# SCH_ODO_2025-04-28.net
KiCad netlist of a schematic drawn in EasyEDA
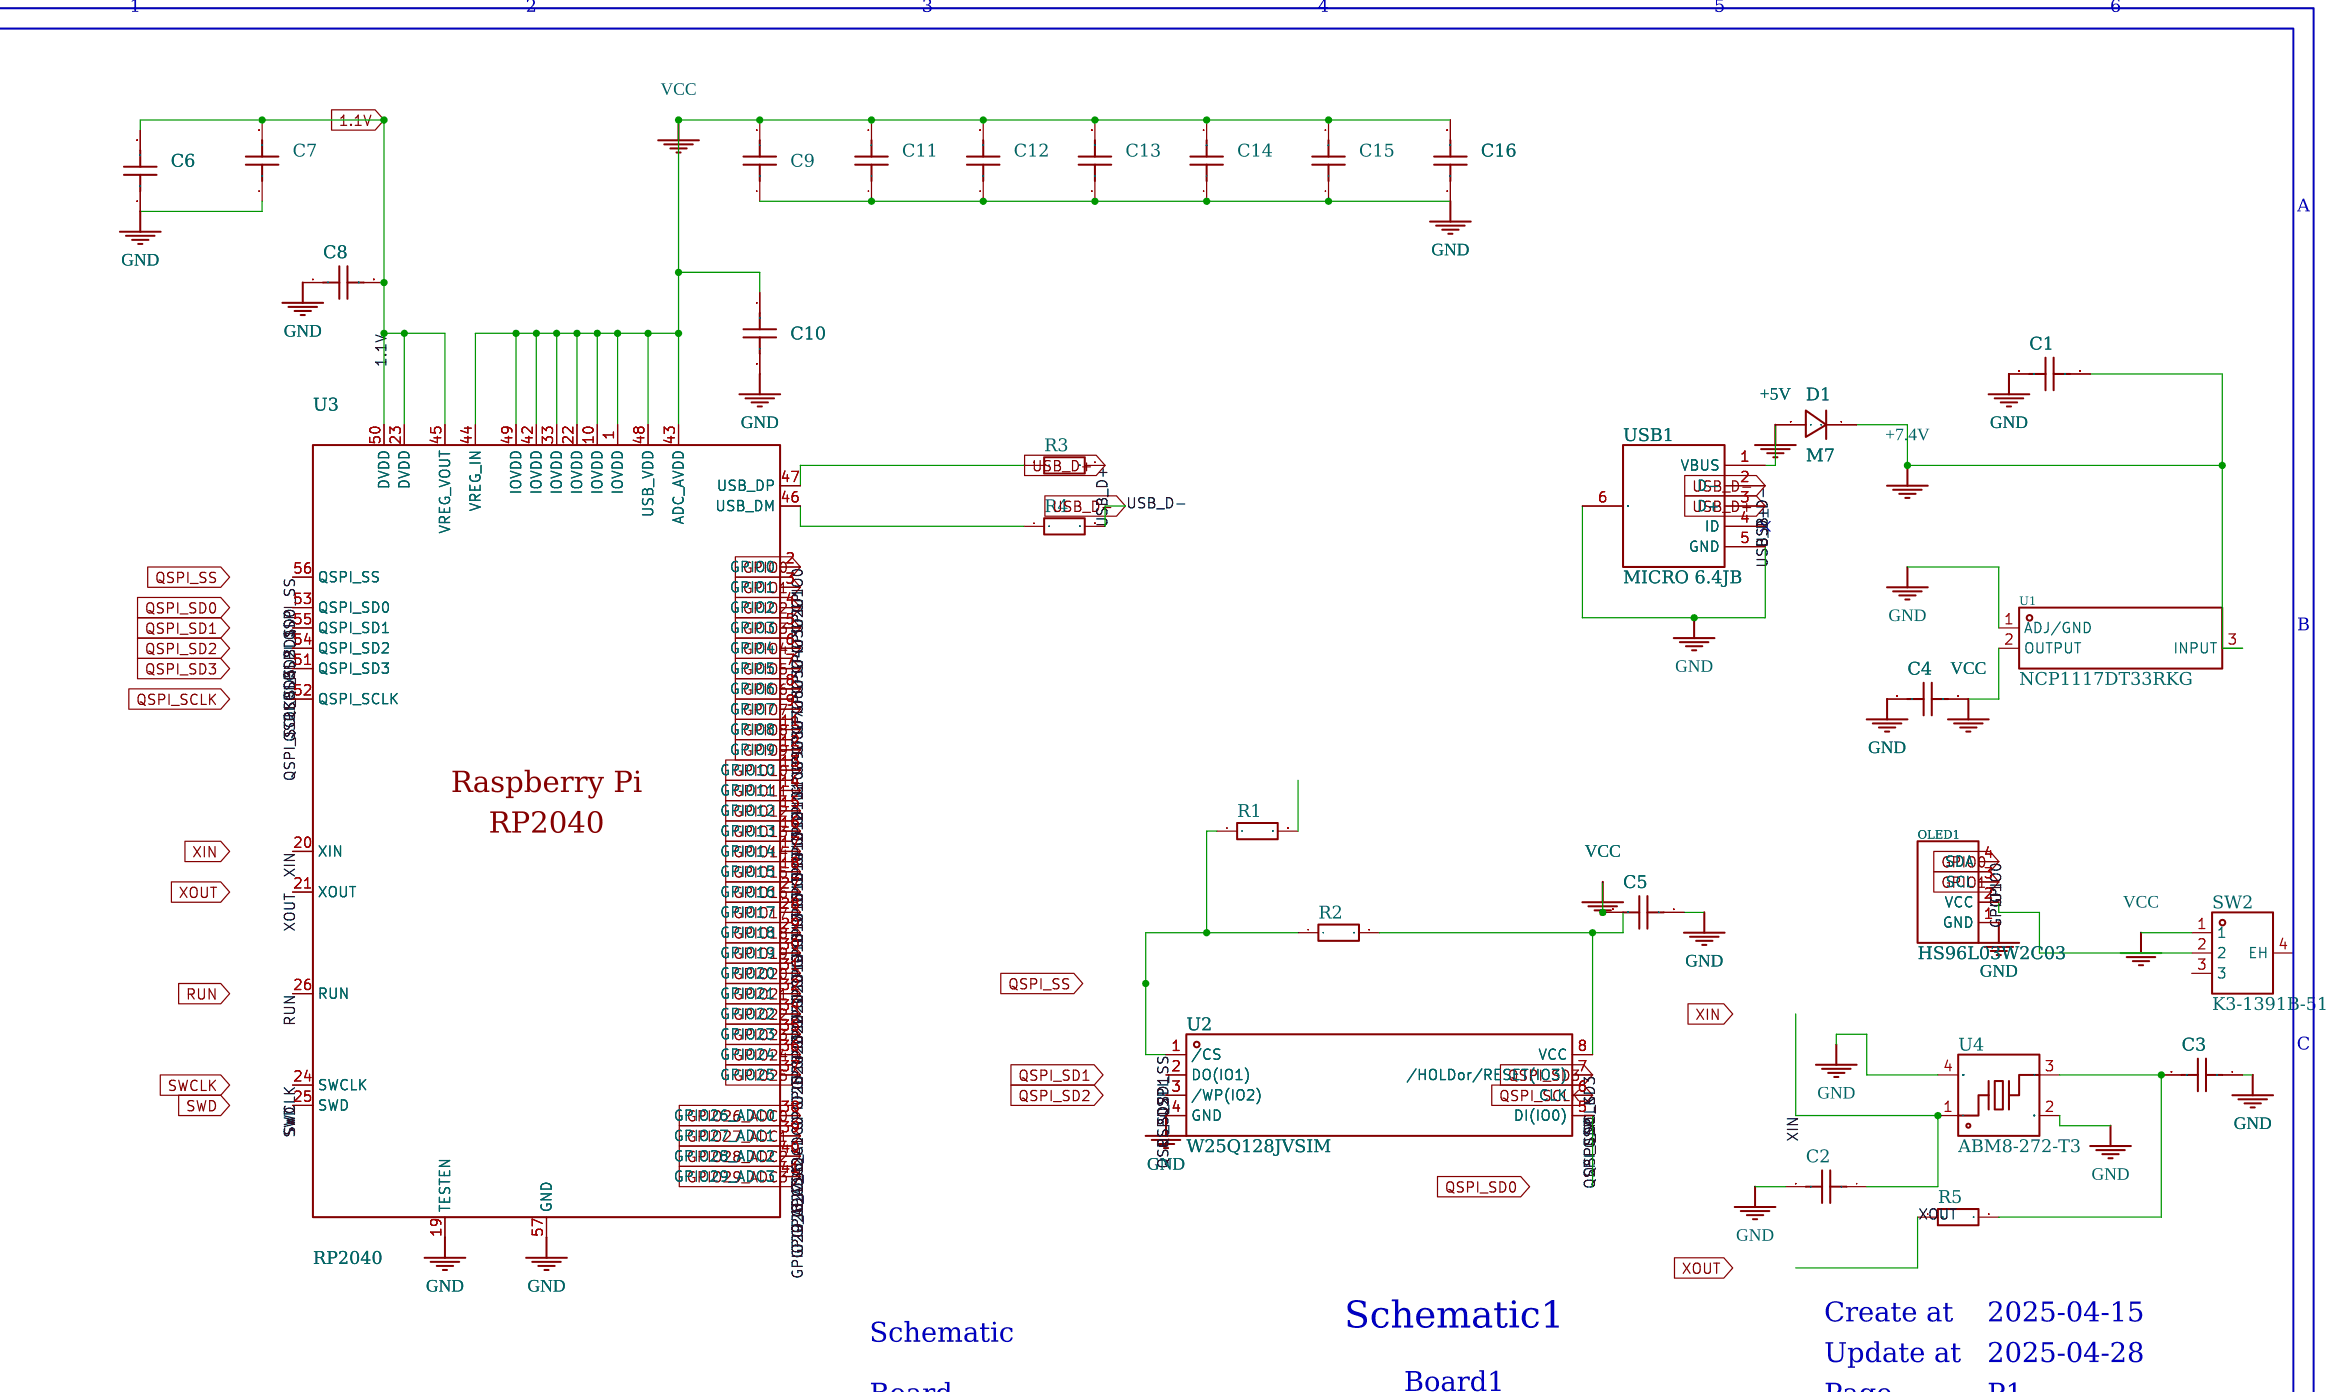
[diagram p0: schematic sheet]

(export (version "E")
  (design (tool "Eeschema 10.0.6"))
  (components
    (comp (ref "C1") (value "10uF") (libsource (lib "") (part "Unknown_1060_-665")))
    (comp (ref "C2") (value "15pF") (libsource (lib "") (part "Unknown_950_-265")))
    (comp (ref "C3") (value "15pF") (libsource (lib "") (part "Unknown_1135_-320")))
    (comp (ref "C4") (value "10uF") (libsource (lib "") (part "Unknown_1000_-505")))
    (comp (ref "C5")
      (value "100nF")
      (fields
        (field (name "Manufacturer Part") "CL05B104KO5NNNC")
        (field (name "Manufacturer") "SAMSUNG(三星)")
      )
      (libsource (lib "") (part "Unknown_860_-400"))
    )
    (comp (ref "C6")
      (value "100nF")
      (fields
        (field (name "Manufacturer Part") "CL05B104KO5NNNC")
        (field (name "Manufacturer") "SAMSUNG(三星)")
      )
      (libsource (lib "") (part "Unknown_120_-765"))
    )
    (comp (ref "C7")
      (value "100nF")
      (fields
        (field (name "Manufacturer Part") "CL05B104KO5NNNC")
        (field (name "Manufacturer") "SAMSUNG(三星)")
      )
      (libsource (lib "") (part "Unknown_180_-770"))
    )
    (comp (ref "C8")
      (value "1uF")
      (fields
        (field (name "Manufacturer Part") "CL05A105KA5NQNC")
        (field (name "Manufacturer") "SAMSUNG(三星)")
      )
      (libsource (lib "") (part "Unknown_220_-710"))
    )
    (comp (ref "C9")
      (value "100nF")
      (fields
        (field (name "Manufacturer Part") "CL05B104KO5NNNC")
        (field (name "Manufacturer") "SAMSUNG(三星)")
      )
      (libsource (lib "") (part "Unknown_425_-770"))
    )
    (comp (ref "C10")
      (value "1uF")
      (fields
        (field (name "Manufacturer Part") "CL05A105KA5NQNC")
        (field (name "Manufacturer") "SAMSUNG(三星)")
      )
      (libsource (lib "") (part "Unknown_425_-685"))
    )
    (comp (ref "C11")
      (value "100nF")
      (fields
        (field (name "Manufacturer Part") "CL05B104KO5NNNC")
        (field (name "Manufacturer") "SAMSUNG(三星)")
      )
      (libsource (lib "") (part "Unknown_480_-770"))
    )
    (comp (ref "C12")
      (value "100nF")
      (fields
        (field (name "Manufacturer Part") "CL05B104KO5NNNC")
        (field (name "Manufacturer") "SAMSUNG(三星)")
      )
      (libsource (lib "") (part "Unknown_535_-770"))
    )
    (comp (ref "C13")
      (value "100nF")
      (fields
        (field (name "Manufacturer Part") "CL05B104KO5NNNC")
        (field (name "Manufacturer") "SAMSUNG(三星)")
      )
      (libsource (lib "") (part "Unknown_590_-770"))
    )
    (comp (ref "C14")
      (value "100nF")
      (fields
        (field (name "Manufacturer Part") "CL05B104KO5NNNC")
        (field (name "Manufacturer") "SAMSUNG(三星)")
      )
      (libsource (lib "") (part "Unknown_645_-770"))
    )
    (comp (ref "C15")
      (value "100nF")
      (fields
        (field (name "Manufacturer Part") "CL05B104KO5NNNC")
        (field (name "Manufacturer") "SAMSUNG(三星)")
      )
      (libsource (lib "") (part "Unknown_705_-770"))
    )
    (comp (ref "C16")
      (value "100nF")
      (fields
        (field (name "Manufacturer Part") "CL05B104KO5NNNC")
        (field (name "Manufacturer") "SAMSUNG(三星)")
      )
      (libsource (lib "") (part "Unknown_765_-770"))
    )
    (comp (ref "D1")
      (value "M7")
      (fields (field (name "Manufacturer") "MDD(辰达半导体)"))
      (libsource (lib "") (part "Unknown_945_-640"))
    )
    (comp (ref "OLED1")
      (value "HS96L03W2C03")
      (fields (field (name "Manufacturer") "HS(汉昇)"))
      (libsource (lib "") (part "Unknown_1015_-410"))
    )
    (comp (ref "R1") (value "1K") (libsource (lib "") (part "Unknown_670_-440")))
    (comp (ref "R2") (value "10K") (libsource (lib "") (part "Unknown_710_-390")))
    (comp (ref "R3") (value "27") (libsource (lib "") (part "Unknown_575_-620")))
    (comp (ref "R4") (value "27") (libsource (lib "") (part "Unknown_575_-590")))
    (comp (ref "R5") (value "1K") (libsource (lib "") (part "Unknown_1015_-250")))
    (comp (ref "SW2")
      (value "K3-1391B-51")
      (fields (field (name "Manufacturer") "韩国韩荣"))
      (libsource (lib "") (part "Unknown_1155_-380"))
    )
    (comp (ref "U1")
      (value "NCP1117DT33RKG")
      (fields (field (name "Manufacturer") "onsemi(安森美)"))
      (libsource (lib "") (part "Unknown_1095_-535"))
    )
    (comp (ref "U2")
      (value "W25Q128JVSIM")
      (fields (field (name "Manufacturer") "WINBOND(华邦)"))
      (libsource (lib "") (part "Unknown_730_-315"))
    )
    (comp (ref "U3")
      (value "RP2040")
      (fields (field (name "Manufacturer") "Raspberry Pi(树莓派)"))
      (libsource (lib "") (part "Unknown_320_-430"))
    )
    (comp (ref "U4")
      (value "ABM8-272-T3")
      (fields (field (name "Manufacturer") "ABRACON"))
      (libsource (lib "") (part "Unknown_1035_-310"))
    )
    (comp (ref "USB1")
      (value "MICRO 6.4JB")
      (fields (field (name "Manufacturer") "SHOU HAN(首韩)"))
      (libsource (lib "") (part "Unknown_880_-600"))
    )
  )
  (nets
    (net (code "1") (name "+5V") (class "Default")
      (node (ref "D1") (pin "2") (pinfunction "A_2") (pintype "unspecified"))
      (node (ref "USB1") (pin "1") (pinfunction "VBUS_1") (pintype "unspecified"))
    )
    (net (code "2") (name "+7.4V") (class "Default")
      (node (ref "C1") (pin "1") (pinfunction "1_1") (pintype "unspecified"))
      (node (ref "D1") (pin "1") (pinfunction "K_1") (pintype "unspecified"))
      (node (ref "U1") (pin "3") (pinfunction "INPUT_3") (pintype "unspecified"))
    )
    (net (code "3") (name "1.1V") (class "Default")
      (node (ref "C6") (pin "2") (pinfunction "2_2") (pintype "unspecified"))
      (node (ref "C7") (pin "2") (pinfunction "2_2") (pintype "unspecified"))
      (node (ref "C8") (pin "2") (pinfunction "2_2") (pintype "unspecified"))
      (node (ref "U3") (pin "23") (pinfunction "DVDD_23") (pintype "unspecified"))
      (node (ref "U3") (pin "45") (pinfunction "VREG_VOUT_45") (pintype "unspecified"))
      (node (ref "U3") (pin "50") (pinfunction "DVDD_50") (pintype "unspecified"))
    )
    (net (code "4") (name "GND") (class "Default")
      (node (ref "C1") (pin "2") (pinfunction "2_2") (pintype "unspecified"))
      (node (ref "C10") (pin "2") (pinfunction "2_2") (pintype "unspecified"))
      (node (ref "C11") (pin "1") (pinfunction "1_1") (pintype "unspecified"))
      (node (ref "C12") (pin "1") (pinfunction "1_1") (pintype "unspecified"))
      (node (ref "C13") (pin "1") (pinfunction "1_1") (pintype "unspecified"))
      (node (ref "C14") (pin "1") (pinfunction "1_1") (pintype "unspecified"))
      (node (ref "C15") (pin "1") (pinfunction "1_1") (pintype "unspecified"))
      (node (ref "C16") (pin "1") (pinfunction "1_1") (pintype "unspecified"))
      (node (ref "C2") (pin "2") (pinfunction "2_2") (pintype "unspecified"))
      (node (ref "C3") (pin "1") (pinfunction "1_1") (pintype "unspecified"))
      (node (ref "C4") (pin "2") (pinfunction "2_2") (pintype "unspecified"))
      (node (ref "C5") (pin "1") (pinfunction "1_1") (pintype "unspecified"))
      (node (ref "C6") (pin "1") (pinfunction "1_1") (pintype "unspecified"))
      (node (ref "C7") (pin "1") (pinfunction "1_1") (pintype "unspecified"))
      (node (ref "C8") (pin "1") (pinfunction "1_1") (pintype "unspecified"))
      (node (ref "C9") (pin "1") (pinfunction "1_1") (pintype "unspecified"))
      (node (ref "OLED1") (pin "1") (pinfunction "GND_1") (pintype "unspecified"))
      (node (ref "U1") (pin "1") (pinfunction "ADJ/GND_1") (pintype "unspecified"))
      (node (ref "U2") (pin "4") (pinfunction "GND_4") (pintype "unspecified"))
      (node (ref "U3") (pin "19") (pinfunction "TESTEN_19") (pintype "unspecified"))
      (node (ref "U3") (pin "57") (pinfunction "GND_57") (pintype "unspecified"))
      (node (ref "U4") (pin "2") (pinfunction "GND_2") (pintype "unspecified"))
      (node (ref "U4") (pin "4") (pinfunction "GND_4") (pintype "unspecified"))
      (node (ref "USB1") (pin "5") (pinfunction "GND_5") (pintype "unspecified"))
      (node (ref "USB1") (pin "6") (pinfunction "EH_6") (pintype "unspecified"))
    )
    (net (code "5") (name "GPIO0") (class "Default")
      (node (ref "OLED1") (pin "4") (pinfunction "SDA_4") (pintype "unspecified"))
      (node (ref "U3") (pin "2") (pinfunction "GPIO0_2") (pintype "unspecified"))
    )
    (net (code "6") (name "GPIO1") (class "Default")
      (node (ref "OLED1") (pin "3") (pinfunction "SCL_3") (pintype "unspecified"))
      (node (ref "U3") (pin "3") (pinfunction "GPIO1_3") (pintype "unspecified"))
    )
    (net (code "7") (name "GPIO2") (class "Default")
      (node (ref "U3") (pin "4") (pinfunction "GPIO2_4") (pintype "unspecified"))
    )
    (net (code "8") (name "GPIO3") (class "Default")
      (node (ref "U3") (pin "5") (pinfunction "GPIO3_5") (pintype "unspecified"))
    )
    (net (code "9") (name "GPIO4") (class "Default")
      (node (ref "U3") (pin "6") (pinfunction "GPIO4_6") (pintype "unspecified"))
    )
    (net (code "10") (name "GPIO5") (class "Default")
      (node (ref "U3") (pin "7") (pinfunction "GPIO5_7") (pintype "unspecified"))
    )
    (net (code "11") (name "GPIO6") (class "Default")
      (node (ref "U3") (pin "8") (pinfunction "GPIO6_8") (pintype "unspecified"))
    )
    (net (code "12") (name "GPIO7") (class "Default")
      (node (ref "U3") (pin "9") (pinfunction "GPIO7_9") (pintype "unspecified"))
    )
    (net (code "13") (name "GPIO8") (class "Default")
      (node (ref "U3") (pin "11") (pinfunction "GPIO8_11") (pintype "unspecified"))
    )
    (net (code "14") (name "GPIO9") (class "Default")
      (node (ref "U3") (pin "12") (pinfunction "GPIO9_12") (pintype "unspecified"))
    )
    (net (code "15") (name "GPIO10") (class "Default")
      (node (ref "U3") (pin "13") (pinfunction "GPIO10_13") (pintype "unspecified"))
    )
    (net (code "16") (name "GPIO11") (class "Default")
      (node (ref "U3") (pin "14") (pinfunction "GPIO11_14") (pintype "unspecified"))
    )
    (net (code "17") (name "GPIO12") (class "Default")
      (node (ref "U3") (pin "15") (pinfunction "GPIO12_15") (pintype "unspecified"))
    )
    (net (code "18") (name "GPIO13") (class "Default")
      (node (ref "U3") (pin "16") (pinfunction "GPIO13_16") (pintype "unspecified"))
    )
    (net (code "19") (name "GPIO14") (class "Default")
      (node (ref "U3") (pin "17") (pinfunction "GPIO14_17") (pintype "unspecified"))
    )
    (net (code "20") (name "GPIO15") (class "Default")
      (node (ref "U3") (pin "18") (pinfunction "GPIO15_18") (pintype "unspecified"))
    )
    (net (code "21") (name "GPIO16") (class "Default")
      (node (ref "U3") (pin "27") (pinfunction "GPIO16_27") (pintype "unspecified"))
    )
    (net (code "22") (name "GPIO17") (class "Default")
      (node (ref "U3") (pin "28") (pinfunction "GPIO17_28") (pintype "unspecified"))
    )
    (net (code "23") (name "GPIO18") (class "Default")
      (node (ref "U3") (pin "29") (pinfunction "GPIO18_29") (pintype "unspecified"))
    )
    (net (code "24") (name "GPIO19") (class "Default")
      (node (ref "U3") (pin "30") (pinfunction "GPIO19_30") (pintype "unspecified"))
    )
    (net (code "25") (name "GPIO20") (class "Default")
      (node (ref "U3") (pin "31") (pinfunction "GPIO20_31") (pintype "unspecified"))
    )
    (net (code "26") (name "GPIO21") (class "Default")
      (node (ref "U3") (pin "32") (pinfunction "GPIO21_32") (pintype "unspecified"))
    )
    (net (code "27") (name "GPIO22") (class "Default")
      (node (ref "U3") (pin "34") (pinfunction "GPIO22_34") (pintype "unspecified"))
    )
    (net (code "28") (name "GPIO23") (class "Default")
      (node (ref "U3") (pin "35") (pinfunction "GPIO23_35") (pintype "unspecified"))
    )
    (net (code "29") (name "GPIO24") (class "Default")
      (node (ref "U3") (pin "36") (pinfunction "GPIO24_36") (pintype "unspecified"))
    )
    (net (code "30") (name "GPIO25") (class "Default")
      (node (ref "U3") (pin "37") (pinfunction "GPIO25_37") (pintype "unspecified"))
    )
    (net (code "31") (name "GPIO26_ADC0") (class "Default")
      (node (ref "U3") (pin "38") (pinfunction "GPIO26_ADC0_38") (pintype "unspecified"))
    )
    (net (code "32") (name "GPIO27_ADC1") (class "Default")
      (node (ref "U3") (pin "39") (pinfunction "GPIO27_ADC1_39") (pintype "unspecified"))
    )
    (net (code "33") (name "GPIO28_ADC2") (class "Default")
      (node (ref "U3") (pin "40") (pinfunction "GPIO28_ADC2_40") (pintype "unspecified"))
    )
    (net (code "34") (name "GPIO29_ADC3") (class "Default")
      (node (ref "U3") (pin "41") (pinfunction "GPIO29_ADC3_41") (pintype "unspecified"))
    )
    (net (code "35") (name "Net-(C3-Pad2)") (class "Default")
      (node (ref "C3") (pin "2") (pinfunction "2_2") (pintype "unspecified"))
      (node (ref "R5") (pin "2") (pinfunction "2_2") (pintype "unspecified"))
      (node (ref "U4") (pin "3") (pinfunction "3_3") (pintype "unspecified"))
    )
    (net (code "36") (name "Net-(OLED1-VCC)") (class "Default")
      (node (ref "OLED1") (pin "2") (pinfunction "VCC_2") (pintype "unspecified"))
      (node (ref "SW2") (pin "2") (pinfunction "2_2") (pintype "unspecified"))
    )
    (net (code "37") (name "Net-(U3-USB_DM)") (class "Default")
      (node (ref "R4") (pin "1") (pinfunction "1_1") (pintype "unspecified"))
      (node (ref "U3") (pin "46") (pinfunction "USB_DM_46") (pintype "unspecified"))
    )
    (net (code "38") (name "Net-(U3-USB_DP)") (class "Default")
      (node (ref "R3") (pin "1") (pinfunction "1_1") (pintype "unspecified"))
      (node (ref "U3") (pin "47") (pinfunction "USB_DP_47") (pintype "unspecified"))
    )
    (net (code "39") (name "QSPI_SCLK") (class "Default")
      (node (ref "U2") (pin "6") (pinfunction "CLK_6") (pintype "unspecified"))
      (node (ref "U3") (pin "52") (pinfunction "QSPI_SCLK_52") (pintype "unspecified"))
    )
    (net (code "40") (name "QSPI_SD0") (class "Default")
      (node (ref "U2") (pin "5") (pinfunction "DI(IO0)_5") (pintype "unspecified"))
      (node (ref "U3") (pin "53") (pinfunction "QSPI_SD0_53") (pintype "unspecified"))
    )
    (net (code "41") (name "QSPI_SD1") (class "Default")
      (node (ref "U2") (pin "2") (pinfunction "DO(IO1)_2") (pintype "unspecified"))
      (node (ref "U3") (pin "55") (pinfunction "QSPI_SD1_55") (pintype "unspecified"))
    )
    (net (code "42") (name "QSPI_SD2") (class "Default")
      (node (ref "U2") (pin "3") (pinfunction "/WP(IO2)_3") (pintype "unspecified"))
      (node (ref "U3") (pin "54") (pinfunction "QSPI_SD2_54") (pintype "unspecified"))
    )
    (net (code "43") (name "QSPI_SD3") (class "Default")
      (node (ref "U2") (pin "7") (pinfunction "/HOLDor/RESET(IO3)_7") (pintype "unspecified"))
      (node (ref "U3") (pin "51") (pinfunction "QSPI_SD3_51") (pintype "unspecified"))
    )
    (net (code "44") (name "QSPI_SS") (class "Default")
      (node (ref "R1") (pin "1") (pinfunction "1_1") (pintype "unspecified"))
      (node (ref "R2") (pin "1") (pinfunction "1_1") (pintype "unspecified"))
      (node (ref "U2") (pin "1") (pinfunction "/CS_1") (pintype "unspecified"))
      (node (ref "U3") (pin "56") (pinfunction "QSPI_SS_56") (pintype "unspecified"))
    )
    (net (code "45") (name "RUN") (class "Default")
      (node (ref "U3") (pin "26") (pinfunction "RUN_26") (pintype "unspecified"))
    )
    (net (code "46") (name "SWCLK") (class "Default")
      (node (ref "U3") (pin "24") (pinfunction "SWCLK_24") (pintype "unspecified"))
    )
    (net (code "47") (name "SWD") (class "Default")
      (node (ref "U3") (pin "25") (pinfunction "SWD_25") (pintype "unspecified"))
    )
    (net (code "48") (name "USB_D+") (class "Default")
      (node (ref "R3") (pin "2") (pinfunction "2_2") (pintype "unspecified"))
      (node (ref "USB1") (pin "3") (pinfunction "D+_3") (pintype "unspecified"))
    )
    (net (code "49") (name "USB_D-") (class "Default")
      (node (ref "R4") (pin "2") (pinfunction "2_2") (pintype "unspecified"))
      (node (ref "USB1") (pin "2") (pinfunction "D-_2") (pintype "unspecified"))
    )
    (net (code "50") (name "VCC") (class "Default")
      (node (ref "C10") (pin "1") (pinfunction "1_1") (pintype "unspecified"))
      (node (ref "C11") (pin "2") (pinfunction "2_2") (pintype "unspecified"))
      (node (ref "C12") (pin "2") (pinfunction "2_2") (pintype "unspecified"))
      (node (ref "C13") (pin "2") (pinfunction "2_2") (pintype "unspecified"))
      (node (ref "C14") (pin "2") (pinfunction "2_2") (pintype "unspecified"))
      (node (ref "C15") (pin "2") (pinfunction "2_2") (pintype "unspecified"))
      (node (ref "C16") (pin "2") (pinfunction "2_2") (pintype "unspecified"))
      (node (ref "C4") (pin "1") (pinfunction "1_1") (pintype "unspecified"))
      (node (ref "C5") (pin "2") (pinfunction "2_2") (pintype "unspecified"))
      (node (ref "C9") (pin "2") (pinfunction "2_2") (pintype "unspecified"))
      (node (ref "R2") (pin "2") (pinfunction "2_2") (pintype "unspecified"))
      (node (ref "SW2") (pin "1") (pinfunction "1_1") (pintype "unspecified"))
      (node (ref "U1") (pin "2") (pinfunction "OUTPUT_2") (pintype "unspecified"))
      (node (ref "U2") (pin "8") (pinfunction "VCC_8") (pintype "unspecified"))
      (node (ref "U3") (pin "1") (pinfunction "IOVDD_1") (pintype "unspecified"))
      (node (ref "U3") (pin "10") (pinfunction "IOVDD_10") (pintype "unspecified"))
      (node (ref "U3") (pin "22") (pinfunction "IOVDD_22") (pintype "unspecified"))
      (node (ref "U3") (pin "33") (pinfunction "IOVDD_33") (pintype "unspecified"))
      (node (ref "U3") (pin "42") (pinfunction "IOVDD_42") (pintype "unspecified"))
      (node (ref "U3") (pin "43") (pinfunction "ADC_AVDD_43") (pintype "unspecified"))
      (node (ref "U3") (pin "44") (pinfunction "VREG_IN_44") (pintype "unspecified"))
      (node (ref "U3") (pin "48") (pinfunction "USB_VDD_48") (pintype "unspecified"))
      (node (ref "U3") (pin "49") (pinfunction "IOVDD_49") (pintype "unspecified"))
    )
    (net (code "51") (name "XIN") (class "Default")
      (node (ref "C2") (pin "1") (pinfunction "1_1") (pintype "unspecified"))
      (node (ref "U3") (pin "20") (pinfunction "XIN_20") (pintype "unspecified"))
      (node (ref "U4") (pin "1") (pinfunction "1_1") (pintype "unspecified"))
    )
    (net (code "52") (name "XOUT") (class "Default")
      (node (ref "R5") (pin "1") (pinfunction "1_1") (pintype "unspecified"))
      (node (ref "U3") (pin "21") (pinfunction "XOUT_21") (pintype "unspecified"))
    )
    (net (code "53") (name "unconnected-(R1-Pad2)") (class "Default")
      (node (ref "R1") (pin "2") (pinfunction "2_2") (pintype "unspecified"))
    )
    (net (code "54") (name "unconnected-(SW2-EH-Pad4)") (class "Default")
      (node (ref "SW2") (pin "4") (pinfunction "EH_4") (pintype "unspecified"))
    )
    (net (code "55") (name "unconnected-(SW2-Pad3)") (class "Default")
      (node (ref "SW2") (pin "3") (pinfunction "3_3") (pintype "unspecified"))
    )
    (net (code "56") (name "unconnected-(USB1-ID-Pad4)") (class "Default")
      (node (ref "USB1") (pin "4") (pinfunction "ID_4") (pintype "unspecified+no_connect"))
    )
  )
)
